# row.net
KiCad netlist of a schematic drawn in EAGLE
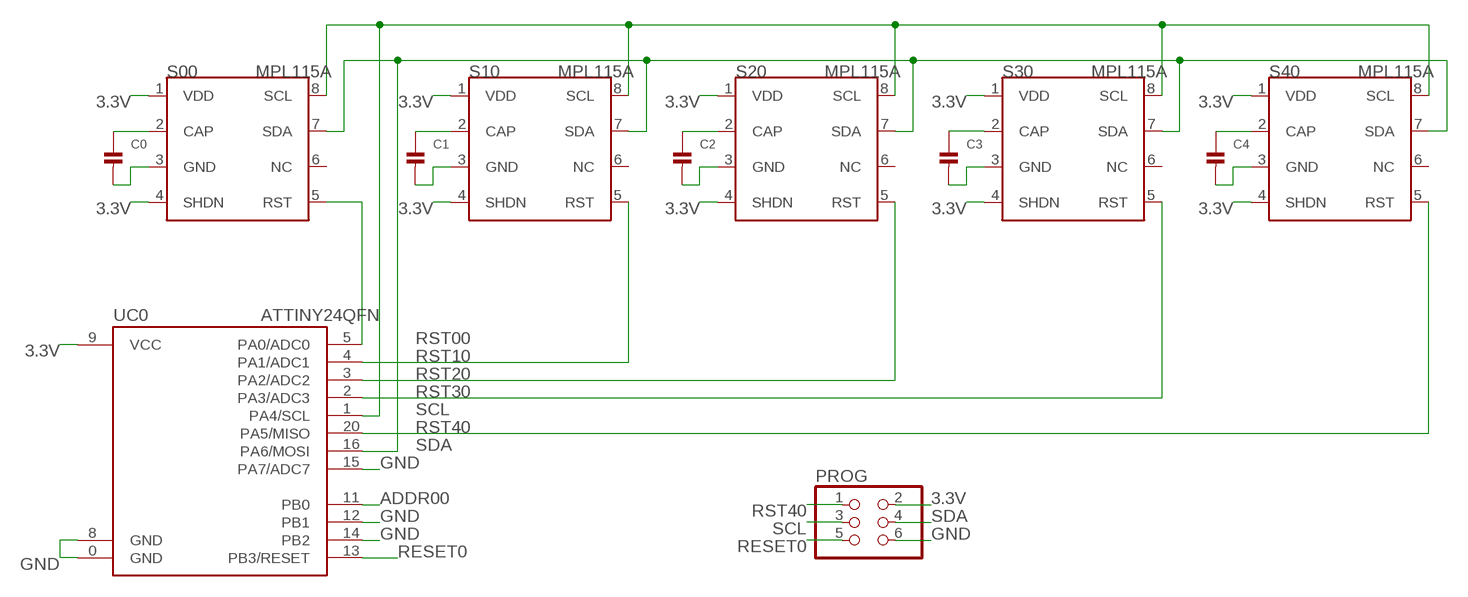
[diagram p0: schematic, sheet 1]

(export (version "E")
  (design (tool "Eeschema 10.0.6"))
  (components
    (comp (ref "C0")
      (value "CAP_CERAMIC0603")
      (footprint "eagle-import:0603")
      (libsource (lib "eagle-import") (part "CAP_CERAMIC0603"))
    )
    (comp (ref "C1")
      (value "CAP_CERAMIC0603")
      (footprint "eagle-import:0603")
      (libsource (lib "eagle-import") (part "CAP_CERAMIC0603"))
    )
    (comp (ref "C2")
      (value "CAP_CERAMIC0603")
      (footprint "eagle-import:0603")
      (libsource (lib "eagle-import") (part "CAP_CERAMIC0603"))
    )
    (comp (ref "C3")
      (value "CAP_CERAMIC0603")
      (footprint "eagle-import:0603")
      (libsource (lib "eagle-import") (part "CAP_CERAMIC0603"))
    )
    (comp (ref "C4")
      (value "CAP_CERAMIC0603")
      (footprint "eagle-import:0603")
      (libsource (lib "eagle-import") (part "CAP_CERAMIC0603"))
    )
    (comp (ref "PROG")
      (value "HEADER-2X3")
      (footprint "eagle-import:2X03")
      (libsource (lib "eagle-import") (part "HEADER-2X3"))
    )
    (comp (ref "S00")
      (value "MPL115A")
      (footprint "eagle-import:LGA-8")
      (libsource (lib "eagle-import") (part "MPL115A"))
    )
    (comp (ref "S10")
      (value "MPL115A")
      (footprint "eagle-import:LGA-8")
      (libsource (lib "eagle-import") (part "MPL115A"))
    )
    (comp (ref "S20")
      (value "MPL115A")
      (footprint "eagle-import:LGA-8")
      (libsource (lib "eagle-import") (part "MPL115A"))
    )
    (comp (ref "S30")
      (value "MPL115A")
      (footprint "eagle-import:LGA-8")
      (libsource (lib "eagle-import") (part "MPL115A"))
    )
    (comp (ref "S40")
      (value "MPL115A")
      (footprint "eagle-import:LGA-8")
      (libsource (lib "eagle-import") (part "MPL115A"))
    )
    (comp (ref "UC0")
      (value "ATTINY24QFN")
      (footprint "eagle-import:QFN20")
      (libsource (lib "eagle-import") (part "ATTINY24QFN"))
    )
  )
  (nets
    (net (code "1") (name "/3.3V") (class "Default")
      (node (ref "PROG") (pin "2") (pinfunction "2_2") (pintype "passive"))
      (node (ref "S00") (pin "1") (pinfunction "VDD_1") (pintype "bidirectional"))
      (node (ref "S00") (pin "4") (pinfunction "SHDN_4") (pintype "bidirectional"))
      (node (ref "S10") (pin "1") (pinfunction "VDD_1") (pintype "bidirectional"))
      (node (ref "S10") (pin "4") (pinfunction "SHDN_4") (pintype "bidirectional"))
      (node (ref "S20") (pin "1") (pinfunction "VDD_1") (pintype "bidirectional"))
      (node (ref "S20") (pin "4") (pinfunction "SHDN_4") (pintype "bidirectional"))
      (node (ref "S30") (pin "1") (pinfunction "VDD_1") (pintype "bidirectional"))
      (node (ref "S30") (pin "4") (pinfunction "SHDN_4") (pintype "bidirectional"))
      (node (ref "S40") (pin "1") (pinfunction "VDD_1") (pintype "bidirectional"))
      (node (ref "S40") (pin "4") (pinfunction "SHDN_4") (pintype "bidirectional"))
      (node (ref "UC0") (pin "9") (pinfunction "VCC_9") (pintype "bidirectional"))
    )
    (net (code "2") (name "/ADDR00") (class "Default")
      (node (ref "UC0") (pin "11") (pinfunction "PB0_11") (pintype "bidirectional"))
    )
    (net (code "3") (name "/GND") (class "Default")
      (node (ref "C0") (pin "2") (pinfunction "P$2_2") (pintype "passive"))
      (node (ref "C1") (pin "2") (pinfunction "P$2_2") (pintype "passive"))
      (node (ref "C2") (pin "2") (pinfunction "P$2_2") (pintype "passive"))
      (node (ref "C3") (pin "2") (pinfunction "P$2_2") (pintype "passive"))
      (node (ref "C4") (pin "2") (pinfunction "P$2_2") (pintype "passive"))
      (node (ref "PROG") (pin "6") (pinfunction "6_6") (pintype "passive"))
      (node (ref "S00") (pin "3") (pinfunction "GND_3") (pintype "bidirectional"))
      (node (ref "S10") (pin "3") (pinfunction "GND_3") (pintype "bidirectional"))
      (node (ref "S20") (pin "3") (pinfunction "GND_3") (pintype "bidirectional"))
      (node (ref "S30") (pin "3") (pinfunction "GND_3") (pintype "bidirectional"))
      (node (ref "S40") (pin "3") (pinfunction "GND_3") (pintype "bidirectional"))
      (node (ref "UC0") (pin "0") (pinfunction "GND_0") (pintype "bidirectional"))
      (node (ref "UC0") (pin "12") (pinfunction "PB1_12") (pintype "bidirectional"))
      (node (ref "UC0") (pin "14") (pinfunction "PB2_14") (pintype "bidirectional"))
      (node (ref "UC0") (pin "15") (pinfunction "PA7/ADC7_15") (pintype "bidirectional"))
      (node (ref "UC0") (pin "8") (pinfunction "GND_8") (pintype "bidirectional"))
    )
    (net (code "4") (name "/RESET0") (class "Default")
      (node (ref "PROG") (pin "5") (pinfunction "5_5") (pintype "passive"))
      (node (ref "UC0") (pin "13") (pinfunction "PB3/RESET_13") (pintype "bidirectional"))
    )
    (net (code "5") (name "/RST00") (class "Default")
      (node (ref "S00") (pin "5") (pinfunction "RST_5") (pintype "bidirectional"))
      (node (ref "UC0") (pin "5") (pinfunction "PA0/ADC0_5") (pintype "bidirectional"))
    )
    (net (code "6") (name "/RST10") (class "Default")
      (node (ref "S10") (pin "5") (pinfunction "RST_5") (pintype "bidirectional"))
      (node (ref "UC0") (pin "4") (pinfunction "PA1/ADC1_4") (pintype "bidirectional"))
    )
    (net (code "7") (name "/RST20") (class "Default")
      (node (ref "S20") (pin "5") (pinfunction "RST_5") (pintype "bidirectional"))
      (node (ref "UC0") (pin "3") (pinfunction "PA2/ADC2_3") (pintype "bidirectional"))
    )
    (net (code "8") (name "/RST30") (class "Default")
      (node (ref "S30") (pin "5") (pinfunction "RST_5") (pintype "bidirectional"))
      (node (ref "UC0") (pin "2") (pinfunction "PA3/ADC3_2") (pintype "bidirectional"))
    )
    (net (code "9") (name "/RST40") (class "Default")
      (node (ref "PROG") (pin "1") (pinfunction "1_1") (pintype "passive"))
      (node (ref "S40") (pin "5") (pinfunction "RST_5") (pintype "bidirectional"))
      (node (ref "UC0") (pin "20") (pinfunction "PA5/MISO_20") (pintype "bidirectional"))
    )
    (net (code "10") (name "/SCL") (class "Default")
      (node (ref "PROG") (pin "3") (pinfunction "3_3") (pintype "passive"))
      (node (ref "S00") (pin "8") (pinfunction "SCL_8") (pintype "bidirectional"))
      (node (ref "S10") (pin "8") (pinfunction "SCL_8") (pintype "bidirectional"))
      (node (ref "S20") (pin "8") (pinfunction "SCL_8") (pintype "bidirectional"))
      (node (ref "S30") (pin "8") (pinfunction "SCL_8") (pintype "bidirectional"))
      (node (ref "S40") (pin "8") (pinfunction "SCL_8") (pintype "bidirectional"))
      (node (ref "UC0") (pin "1") (pinfunction "PA4/SCL_1") (pintype "bidirectional"))
    )
    (net (code "11") (name "/SDA") (class "Default")
      (node (ref "PROG") (pin "4") (pinfunction "4_4") (pintype "passive"))
      (node (ref "S00") (pin "7") (pinfunction "SDA_7") (pintype "bidirectional"))
      (node (ref "S10") (pin "7") (pinfunction "SDA_7") (pintype "bidirectional"))
      (node (ref "S20") (pin "7") (pinfunction "SDA_7") (pintype "bidirectional"))
      (node (ref "S30") (pin "7") (pinfunction "SDA_7") (pintype "bidirectional"))
      (node (ref "S40") (pin "7") (pinfunction "SDA_7") (pintype "bidirectional"))
      (node (ref "UC0") (pin "16") (pinfunction "PA6/MOSI_16") (pintype "bidirectional"))
    )
    (net (code "12") (name "Net-(C0-P$1)") (class "Default")
      (node (ref "C0") (pin "1") (pinfunction "P$1_1") (pintype "passive"))
      (node (ref "S00") (pin "2") (pinfunction "CAP_2") (pintype "bidirectional"))
    )
    (net (code "13") (name "Net-(C1-P$1)") (class "Default")
      (node (ref "C1") (pin "1") (pinfunction "P$1_1") (pintype "passive"))
      (node (ref "S10") (pin "2") (pinfunction "CAP_2") (pintype "bidirectional"))
    )
    (net (code "14") (name "Net-(C2-P$1)") (class "Default")
      (node (ref "C2") (pin "1") (pinfunction "P$1_1") (pintype "passive"))
      (node (ref "S20") (pin "2") (pinfunction "CAP_2") (pintype "bidirectional"))
    )
    (net (code "15") (name "Net-(C3-P$1)") (class "Default")
      (node (ref "C3") (pin "1") (pinfunction "P$1_1") (pintype "passive"))
      (node (ref "S30") (pin "2") (pinfunction "CAP_2") (pintype "bidirectional"))
    )
    (net (code "16") (name "Net-(C4-P$1)") (class "Default")
      (node (ref "C4") (pin "1") (pinfunction "P$1_1") (pintype "passive"))
      (node (ref "S40") (pin "2") (pinfunction "CAP_2") (pintype "bidirectional"))
    )
    (net (code "17") (name "unconnected-(S00-NC-Pad6)") (class "Default")
      (node (ref "S00") (pin "6") (pinfunction "NC_6") (pintype "bidirectional"))
    )
    (net (code "18") (name "unconnected-(S10-NC-Pad6)") (class "Default")
      (node (ref "S10") (pin "6") (pinfunction "NC_6") (pintype "bidirectional"))
    )
    (net (code "19") (name "unconnected-(S20-NC-Pad6)") (class "Default")
      (node (ref "S20") (pin "6") (pinfunction "NC_6") (pintype "bidirectional"))
    )
    (net (code "20") (name "unconnected-(S30-NC-Pad6)") (class "Default")
      (node (ref "S30") (pin "6") (pinfunction "NC_6") (pintype "bidirectional"))
    )
    (net (code "21") (name "unconnected-(S40-NC-Pad6)") (class "Default")
      (node (ref "S40") (pin "6") (pinfunction "NC_6") (pintype "bidirectional"))
    )
  )
)
